# tower_controller.net
KiCad netlist of a schematic drawn in EAGLE
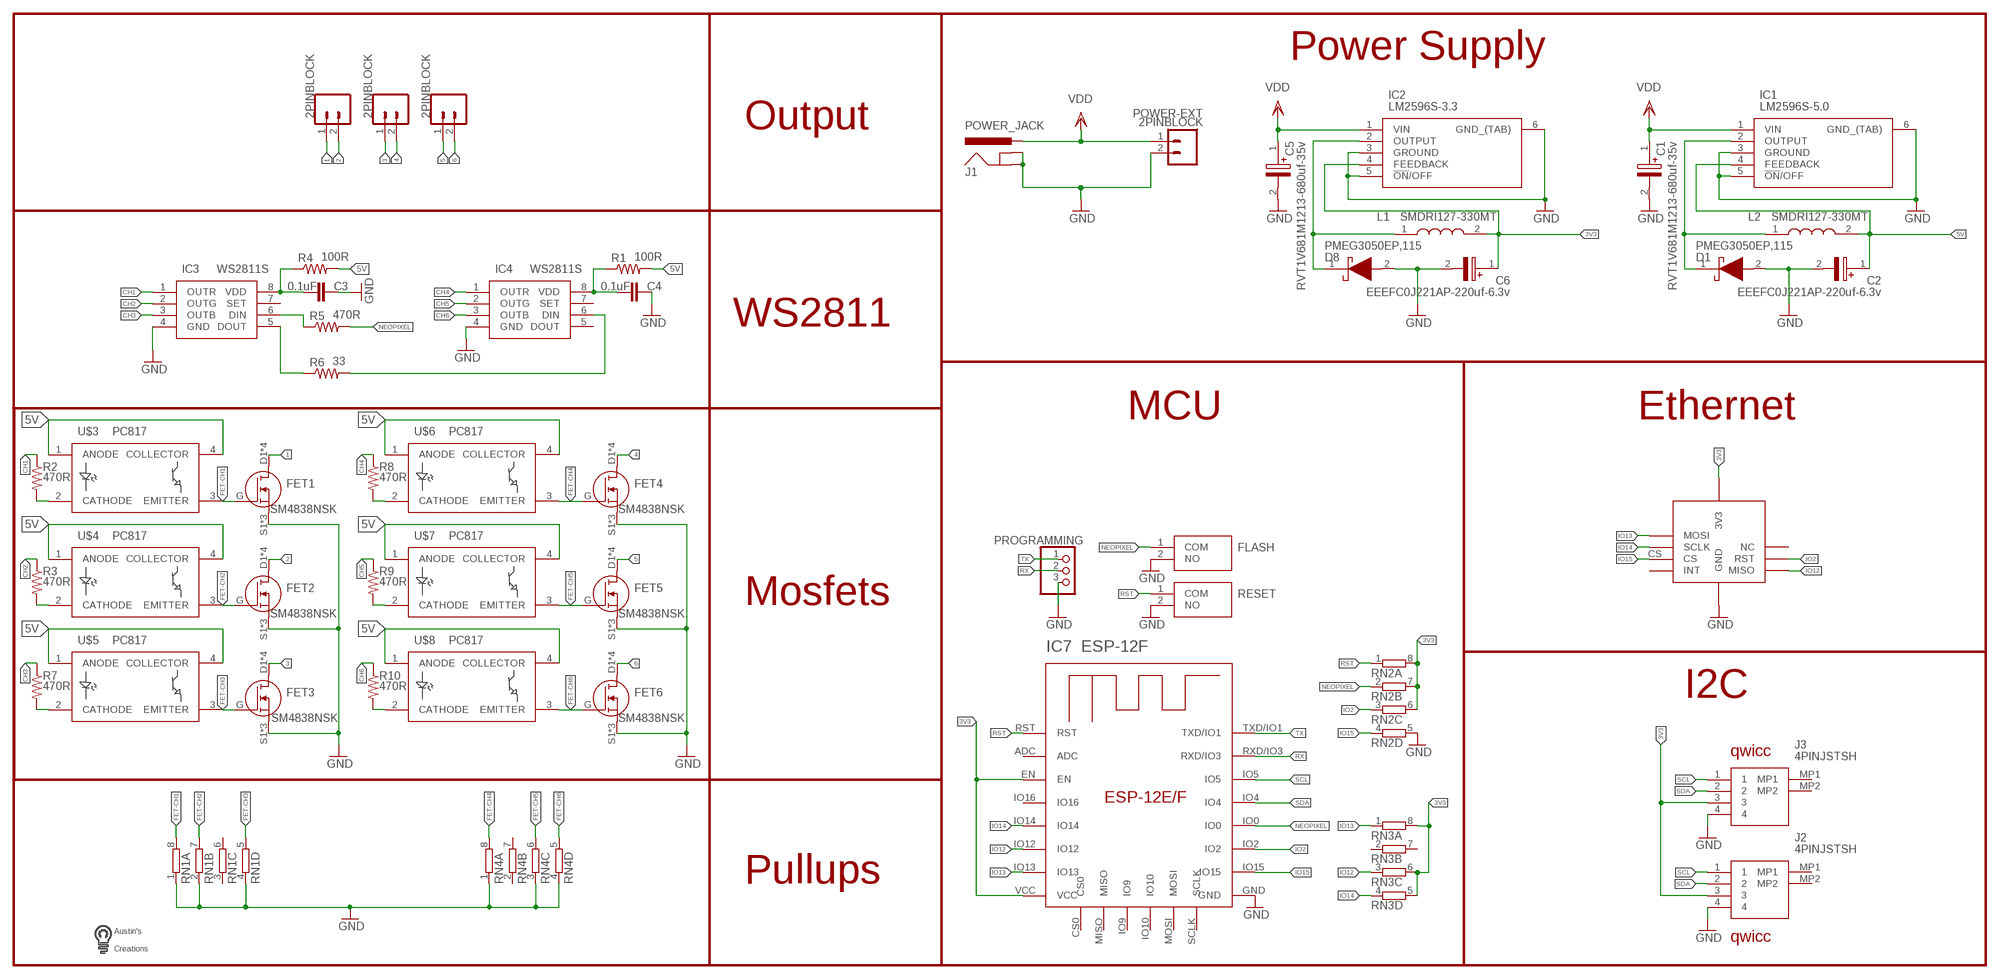
[diagram p0: schematic, sheet 1]

(export (version "E")
  (design (tool "Eeschema 10.0.6"))
  (components
    (comp (ref "C1")
      (value "RVT1V681M1213-680uf-35v")
      (footprint "eagle-import:CAPAE1350X1400N")
      (fields
        (field (name "MANUFACTURER_PART_NUMBER") "EEE-HD1V681AQ")
        (field (name "MOUSER_PART_NUMBER") "667-EEE-HD1V681AQ")
      )
      (libsource (lib "eagle-import") (part "EEE-HD1V681AQ"))
    )
    (comp (ref "C2")
      (value "EEEFC0J221AP-220uf-6.3v")
      (footprint "eagle-import:CAPAE830X650N")
      (fields (field (name "MANUFACTURER_PART_NUMBER") "EEEFC0J221AP"))
      (libsource (lib "eagle-import") (part "EEEFC0J221AP"))
    )
    (comp (ref "C3")
      (value "0.1uF")
      (footprint "eagle-import:C0603")
      (libsource (lib "eagle-import") (part "C-EUC0603"))
    )
    (comp (ref "C4")
      (value "0.1uF")
      (footprint "eagle-import:C0603")
      (libsource (lib "eagle-import") (part "C-EUC0603"))
    )
    (comp (ref "C5")
      (value "RVT1V681M1213-680uf-35v")
      (footprint "eagle-import:CAPAE1350X1400N")
      (fields
        (field (name "MANUFACTURER_PART_NUMBER") "EEE-HD1V681AQ")
        (field (name "MOUSER_PART_NUMBER") "667-EEE-HD1V681AQ")
      )
      (libsource (lib "eagle-import") (part "EEE-HD1V681AQ"))
    )
    (comp (ref "C6")
      (value "EEEFC0J221AP-220uf-6.3v")
      (footprint "eagle-import:CAPAE830X650N")
      (fields (field (name "MANUFACTURER_PART_NUMBER") "EEEFC0J221AP"))
      (libsource (lib "eagle-import") (part "EEEFC0J221AP"))
    )
    (comp (ref "D1")
      (value "PMEG3050EP,115")
      (footprint "eagle-import:PMEG3050EP115")
      (fields (field (name "MOUSER_PART_NUMBER") "771-PMEG3050EP115"))
      (libsource (lib "eagle-import") (part "PMEG3050EP,115"))
    )
    (comp (ref "D8")
      (value "PMEG3050EP,115")
      (footprint "eagle-import:PMEG3050EP115")
      (fields (field (name "MOUSER_PART_NUMBER") "771-PMEG3050EP115"))
      (libsource (lib "eagle-import") (part "PMEG3050EP,115"))
    )
    (comp (ref "FET1")
      (value "SM4838NSK")
      (footprint "eagle-import:SM4838NSK")
      (libsource (lib "eagle-import") (part "SM4838NSK"))
    )
    (comp (ref "FET2")
      (value "SM4838NSK")
      (footprint "eagle-import:SM4838NSK")
      (libsource (lib "eagle-import") (part "SM4838NSK"))
    )
    (comp (ref "FET3")
      (value "SM4838NSK")
      (footprint "eagle-import:SM4838NSK")
      (libsource (lib "eagle-import") (part "SM4838NSK"))
    )
    (comp (ref "FET4")
      (value "SM4838NSK")
      (footprint "eagle-import:SM4838NSK")
      (libsource (lib "eagle-import") (part "SM4838NSK"))
    )
    (comp (ref "FET5")
      (value "SM4838NSK")
      (footprint "eagle-import:SM4838NSK")
      (libsource (lib "eagle-import") (part "SM4838NSK"))
    )
    (comp (ref "FET6")
      (value "SM4838NSK")
      (footprint "eagle-import:SM4838NSK")
      (libsource (lib "eagle-import") (part "SM4838NSK"))
    )
    (comp (ref "FLASH")
      (value "PTS636_SM25F_SMTR_LFS")
      (footprint "eagle-import:PTS636SM25FSMTRLFS")
      (fields
        (field (name "ARROW_PART_NUMBER") "PTS636 SM25F SMTR LFS")
        (field (name "MOUSER_PART_NUMBER") "611-PTS636SM25FSMTRL")
      )
      (libsource (lib "eagle-import") (part "PTS636_SM25F_SMTR_LFS"))
    )
    (comp (ref "GND")
      (value "2PINBLOCK")
      (footprint "eagle-import:SCREWTERMINAL-5MM-2")
      (libsource (lib "eagle-import") (part "2PINBLOCK"))
    )
    (comp (ref "GND10")
      (value "2PINBLOCK")
      (footprint "eagle-import:SCREWTERMINAL-5MM-2")
      (libsource (lib "eagle-import") (part "2PINBLOCK"))
    )
    (comp (ref "GND11")
      (value "2PINBLOCK")
      (footprint "eagle-import:SCREWTERMINAL-5MM-2")
      (libsource (lib "eagle-import") (part "2PINBLOCK"))
    )
    (comp (ref "IC1")
      (value "LM2596S-5.0")
      (footprint "eagle-import:TO170P1435X465-6N")
      (fields
        (field (name "MANUFACTURER_PART_NUMBER") "LM2596S-3.3/NOPB")
        (field (name "MOUSER_PART_NUMBER") "926-LM2596S-3.3/NOPB")
      )
      (libsource (lib "eagle-import") (part "LM2596S-3.3_NOPB"))
    )
    (comp (ref "IC2")
      (value "LM2596S-3.3")
      (footprint "eagle-import:TO170P1435X465-6N")
      (fields
        (field (name "MANUFACTURER_PART_NUMBER") "LM2596S-3.3/NOPB")
        (field (name "MOUSER_PART_NUMBER") "926-LM2596S-3.3/NOPB")
      )
      (libsource (lib "eagle-import") (part "LM2596S-3.3_NOPB"))
    )
    (comp (ref "IC3")
      (value "WS2811S")
      (footprint "eagle-import:SOIC127P600X175-8N")
      (fields (field (name "MANUFACTURER_PART_NUMBER") "ws2811s"))
      (libsource (lib "eagle-import") (part "WS2811S"))
    )
    (comp (ref "IC4")
      (value "WS2811S")
      (footprint "eagle-import:SOIC127P600X175-8N")
      (fields (field (name "MANUFACTURER_PART_NUMBER") "ws2811s"))
      (libsource (lib "eagle-import") (part "WS2811S"))
    )
    (comp (ref "IC7")
      (value "ESP-12F")
      (footprint "eagle-import:ESP-12E")
      (libsource (lib "eagle-import") (part "ESP-12E/F"))
    )
    (comp (ref "J1")
      (value "POWER_JACK")
      (footprint "eagle-import:POWER_JACK_PTH")
      (libsource (lib "eagle-import") (part "POWER_JACK"))
    )
    (comp (ref "J2")
      (value "4PINJSTSH")
      (footprint "eagle-import:665104131822")
      (fields
        (field (name "MANUFACTURER_PART_NUMBER") "665104131822")
        (field (name "MOUSER_PART_NUMBER") "710-665104131822")
      )
      (libsource (lib "eagle-import") (part "4PINJSTSH"))
    )
    (comp (ref "J3")
      (value "4PINJSTSH")
      (footprint "eagle-import:665104131822")
      (fields
        (field (name "MANUFACTURER_PART_NUMBER") "665104131822")
        (field (name "MOUSER_PART_NUMBER") "710-665104131822")
      )
      (libsource (lib "eagle-import") (part "4PINJSTSH"))
    )
    (comp (ref "L1")
      (value "SMDRI127-330MT")
      (footprint "eagle-import:INDPM120120X800N")
      (fields
        (field (name "MANUFACTURER_PART_NUMBER") "CDRH127/LDNP-330MC")
        (field (name "MOUSER_PART_NUMBER") "851-CDRH127LDNP330MC")
      )
      (libsource (lib "eagle-import") (part "CDRH127_LDNP-330MC"))
    )
    (comp (ref "L2")
      (value "SMDRI127-330MT")
      (footprint "eagle-import:INDPM120120X800N")
      (fields
        (field (name "MANUFACTURER_PART_NUMBER") "CDRH127/LDNP-330MC")
        (field (name "MOUSER_PART_NUMBER") "851-CDRH127LDNP330MC")
      )
      (libsource (lib "eagle-import") (part "CDRH127_LDNP-330MC"))
    )
    (comp (ref "POWER-EXT")
      (value "2PINBLOCK")
      (footprint "eagle-import:SCREWTERMINAL-5MM-2")
      (libsource (lib "eagle-import") (part "2PINBLOCK"))
    )
    (comp (ref "PROGRAMMING")
      (value "PINHD-1X3")
      (footprint "eagle-import:1X03")
      (libsource (lib "eagle-import") (part "PINHD-1X3"))
    )
    (comp (ref "R1")
      (value "100R")
      (footprint "eagle-import:R0603")
      (libsource (lib "eagle-import") (part "R-US_R0603"))
    )
    (comp (ref "R2")
      (value "470R")
      (footprint "eagle-import:R0603")
      (libsource (lib "eagle-import") (part "R-US_R0603"))
    )
    (comp (ref "R3")
      (value "470R")
      (footprint "eagle-import:R0603")
      (libsource (lib "eagle-import") (part "R-US_R0603"))
    )
    (comp (ref "R4")
      (value "100R")
      (footprint "eagle-import:R0603")
      (libsource (lib "eagle-import") (part "R-US_R0603"))
    )
    (comp (ref "R5")
      (value "470R")
      (footprint "eagle-import:R0603")
      (libsource (lib "eagle-import") (part "R-US_R0603"))
    )
    (comp (ref "R6")
      (value "33")
      (footprint "eagle-import:R0603")
      (libsource (lib "eagle-import") (part "R-US_R0603"))
    )
    (comp (ref "R7")
      (value "470R")
      (footprint "eagle-import:R0603")
      (libsource (lib "eagle-import") (part "R-US_R0603"))
    )
    (comp (ref "R8")
      (value "470R")
      (footprint "eagle-import:R0603")
      (libsource (lib "eagle-import") (part "R-US_R0603"))
    )
    (comp (ref "R9")
      (value "470R")
      (footprint "eagle-import:R0603")
      (libsource (lib "eagle-import") (part "R-US_R0603"))
    )
    (comp (ref "R10")
      (value "470R")
      (footprint "eagle-import:R0603")
      (libsource (lib "eagle-import") (part "R-US_R0603"))
    )
    (comp (ref "RESET")
      (value "PTS636_SM25F_SMTR_LFS")
      (footprint "eagle-import:PTS636SM25FSMTRLFS")
      (fields
        (field (name "ARROW_PART_NUMBER") "PTS636 SM25F SMTR LFS")
        (field (name "MOUSER_PART_NUMBER") "611-PTS636SM25FSMTRL")
      )
      (libsource (lib "eagle-import") (part "PTS636_SM25F_SMTR_LFS"))
    )
    (comp (ref "RN1")
      (value "4R-N0603-ARC")
      (footprint "eagle-import:0603-ARC")
      (libsource (lib "eagle-import") (part "4R-N0603-ARC"))
    )
    (comp (ref "RN2")
      (value "4R-N0603-ARC")
      (footprint "eagle-import:0603-ARC")
      (libsource (lib "eagle-import") (part "4R-N0603-ARC"))
    )
    (comp (ref "RN3")
      (value "4R-N0603-ARC")
      (footprint "eagle-import:0603-ARC")
      (libsource (lib "eagle-import") (part "4R-N0603-ARC"))
    )
    (comp (ref "RN4")
      (value "4R-N0603-ARC")
      (footprint "eagle-import:0603-ARC")
      (libsource (lib "eagle-import") (part "4R-N0603-ARC"))
    )
    (comp (ref "U$1")
      (value "W5500MODULE")
      (footprint "eagle-import:W5500MODULE")
      (libsource (lib "eagle-import") (part "W5500MODULE"))
    )
    (comp (ref "U$2")
      (value "LOGOMED")
      (footprint "eagle-import:LOGOMED")
      (libsource (lib "eagle-import") (part "LOGOMED"))
    )
    (comp (ref "U$3")
      (value "PC817")
      (footprint "eagle-import:SOP254P960X420-4N")
      (libsource (lib "eagle-import") (part "PC817"))
    )
    (comp (ref "U$4")
      (value "PC817")
      (footprint "eagle-import:SOP254P960X420-4N")
      (libsource (lib "eagle-import") (part "PC817"))
    )
    (comp (ref "U$5")
      (value "PC817")
      (footprint "eagle-import:SOP254P960X420-4N")
      (libsource (lib "eagle-import") (part "PC817"))
    )
    (comp (ref "U$6")
      (value "PC817")
      (footprint "eagle-import:SOP254P960X420-4N")
      (libsource (lib "eagle-import") (part "PC817"))
    )
    (comp (ref "U$7")
      (value "PC817")
      (footprint "eagle-import:SOP254P960X420-4N")
      (libsource (lib "eagle-import") (part "PC817"))
    )
    (comp (ref "U$8")
      (value "PC817")
      (footprint "eagle-import:SOP254P960X420-4N")
      (libsource (lib "eagle-import") (part "PC817"))
    )
  )
  (nets
    (net (code "1") (name "1") (class "Default")
      (node (ref "FET1") (pin "D1") (pinfunction "D_D1") (pintype "bidirectional"))
      (node (ref "FET1") (pin "D2") (pinfunction "D_D2") (pintype "bidirectional"))
      (node (ref "FET1") (pin "D3") (pinfunction "D_D3") (pintype "bidirectional"))
      (node (ref "FET1") (pin "D4") (pinfunction "D_D4") (pintype "bidirectional"))
      (node (ref "GND") (pin "1") (pinfunction "1_1") (pintype "passive"))
    )
    (net (code "2") (name "2") (class "Default")
      (node (ref "FET2") (pin "D1") (pinfunction "D_D1") (pintype "bidirectional"))
      (node (ref "FET2") (pin "D2") (pinfunction "D_D2") (pintype "bidirectional"))
      (node (ref "FET2") (pin "D3") (pinfunction "D_D3") (pintype "bidirectional"))
      (node (ref "FET2") (pin "D4") (pinfunction "D_D4") (pintype "bidirectional"))
      (node (ref "GND") (pin "2") (pinfunction "2_2") (pintype "passive"))
    )
    (net (code "3") (name "3") (class "Default")
      (node (ref "FET3") (pin "D1") (pinfunction "D_D1") (pintype "bidirectional"))
      (node (ref "FET3") (pin "D2") (pinfunction "D_D2") (pintype "bidirectional"))
      (node (ref "FET3") (pin "D3") (pinfunction "D_D3") (pintype "bidirectional"))
      (node (ref "FET3") (pin "D4") (pinfunction "D_D4") (pintype "bidirectional"))
      (node (ref "GND10") (pin "1") (pinfunction "1_1") (pintype "passive"))
    )
    (net (code "4") (name "3V3") (class "Default")
      (node (ref "C6") (pin "1") (pinfunction "+_1") (pintype "bidirectional"))
      (node (ref "IC2") (pin "4") (pinfunction "FEEDBACK_4") (pintype "bidirectional"))
      (node (ref "IC7") (pin "EN") (pinfunction "EN_EN") (pintype "bidirectional"))
      (node (ref "IC7") (pin "VCC") (pinfunction "VCC_VCC") (pintype "power_in"))
      (node (ref "J2") (pin "3") (pinfunction "3_3") (pintype "bidirectional"))
      (node (ref "J3") (pin "3") (pinfunction "3_3") (pintype "bidirectional"))
      (node (ref "L1") (pin "2") (pinfunction "2_2") (pintype "bidirectional"))
      (node (ref "RN2") (pin "6") (pinfunction "2_6") (pintype "passive"))
      (node (ref "RN2") (pin "7") (pinfunction "2_7") (pintype "passive"))
      (node (ref "RN2") (pin "8") (pinfunction "2_8") (pintype "passive"))
      (node (ref "RN3") (pin "5") (pinfunction "2_5") (pintype "passive"))
      (node (ref "RN3") (pin "6") (pinfunction "2_6") (pintype "passive"))
      (node (ref "RN3") (pin "8") (pinfunction "2_8") (pintype "passive"))
      (node (ref "U$1") (pin "3V3_1") (pinfunction "3V3_3V3_1") (pintype "bidirectional"))
      (node (ref "U$1") (pin "3V3_2") (pinfunction "3V3_3V3_2") (pintype "bidirectional"))
    )
    (net (code "5") (name "4") (class "Default")
      (node (ref "FET4") (pin "D1") (pinfunction "D_D1") (pintype "bidirectional"))
      (node (ref "FET4") (pin "D2") (pinfunction "D_D2") (pintype "bidirectional"))
      (node (ref "FET4") (pin "D3") (pinfunction "D_D3") (pintype "bidirectional"))
      (node (ref "FET4") (pin "D4") (pinfunction "D_D4") (pintype "bidirectional"))
      (node (ref "GND10") (pin "2") (pinfunction "2_2") (pintype "passive"))
    )
    (net (code "6") (name "5") (class "Default")
      (node (ref "FET5") (pin "D1") (pinfunction "D_D1") (pintype "bidirectional"))
      (node (ref "FET5") (pin "D2") (pinfunction "D_D2") (pintype "bidirectional"))
      (node (ref "FET5") (pin "D3") (pinfunction "D_D3") (pintype "bidirectional"))
      (node (ref "FET5") (pin "D4") (pinfunction "D_D4") (pintype "bidirectional"))
      (node (ref "GND11") (pin "1") (pinfunction "1_1") (pintype "passive"))
    )
    (net (code "7") (name "5V") (class "Default")
      (node (ref "C2") (pin "1") (pinfunction "+_1") (pintype "bidirectional"))
      (node (ref "IC1") (pin "4") (pinfunction "FEEDBACK_4") (pintype "bidirectional"))
      (node (ref "L2") (pin "2") (pinfunction "2_2") (pintype "bidirectional"))
      (node (ref "R1") (pin "2") (pinfunction "2_2") (pintype "passive"))
      (node (ref "R4") (pin "2") (pinfunction "2_2") (pintype "passive"))
      (node (ref "U$3") (pin "1") (pinfunction "ANODE_1") (pintype "bidirectional"))
      (node (ref "U$3") (pin "4") (pinfunction "COLLECTOR_4") (pintype "bidirectional"))
      (node (ref "U$4") (pin "1") (pinfunction "ANODE_1") (pintype "bidirectional"))
      (node (ref "U$4") (pin "4") (pinfunction "COLLECTOR_4") (pintype "bidirectional"))
      (node (ref "U$5") (pin "1") (pinfunction "ANODE_1") (pintype "bidirectional"))
      (node (ref "U$5") (pin "4") (pinfunction "COLLECTOR_4") (pintype "bidirectional"))
      (node (ref "U$6") (pin "1") (pinfunction "ANODE_1") (pintype "bidirectional"))
      (node (ref "U$6") (pin "4") (pinfunction "COLLECTOR_4") (pintype "bidirectional"))
      (node (ref "U$7") (pin "1") (pinfunction "ANODE_1") (pintype "bidirectional"))
      (node (ref "U$7") (pin "4") (pinfunction "COLLECTOR_4") (pintype "bidirectional"))
      (node (ref "U$8") (pin "1") (pinfunction "ANODE_1") (pintype "bidirectional"))
      (node (ref "U$8") (pin "4") (pinfunction "COLLECTOR_4") (pintype "bidirectional"))
    )
    (net (code "8") (name "6") (class "Default")
      (node (ref "FET6") (pin "D1") (pinfunction "D_D1") (pintype "bidirectional"))
      (node (ref "FET6") (pin "D2") (pinfunction "D_D2") (pintype "bidirectional"))
      (node (ref "FET6") (pin "D3") (pinfunction "D_D3") (pintype "bidirectional"))
      (node (ref "FET6") (pin "D4") (pinfunction "D_D4") (pintype "bidirectional"))
      (node (ref "GND11") (pin "2") (pinfunction "2_2") (pintype "passive"))
    )
    (net (code "9") (name "CH1") (class "Default")
      (node (ref "IC3") (pin "1") (pinfunction "OUTR_1") (pintype "output"))
      (node (ref "R2") (pin "1") (pinfunction "1_1") (pintype "passive"))
    )
    (net (code "10") (name "CH2") (class "Default")
      (node (ref "IC3") (pin "2") (pinfunction "OUTG_2") (pintype "output"))
      (node (ref "R3") (pin "1") (pinfunction "1_1") (pintype "passive"))
    )
    (net (code "11") (name "CH3") (class "Default")
      (node (ref "IC3") (pin "3") (pinfunction "OUTB_3") (pintype "output"))
      (node (ref "R7") (pin "1") (pinfunction "1_1") (pintype "passive"))
    )
    (net (code "12") (name "CH4") (class "Default")
      (node (ref "IC4") (pin "1") (pinfunction "OUTR_1") (pintype "output"))
      (node (ref "R8") (pin "1") (pinfunction "1_1") (pintype "passive"))
    )
    (net (code "13") (name "CH5") (class "Default")
      (node (ref "IC4") (pin "2") (pinfunction "OUTG_2") (pintype "output"))
      (node (ref "R9") (pin "1") (pinfunction "1_1") (pintype "passive"))
    )
    (net (code "14") (name "CH6") (class "Default")
      (node (ref "IC4") (pin "3") (pinfunction "OUTB_3") (pintype "output"))
      (node (ref "R10") (pin "1") (pinfunction "1_1") (pintype "passive"))
    )
    (net (code "15") (name "FET-CH1") (class "Default")
      (node (ref "FET1") (pin "G") (pinfunction "G_G") (pintype "bidirectional"))
      (node (ref "RN1") (pin "8") (pinfunction "2_8") (pintype "passive"))
      (node (ref "U$3") (pin "3") (pinfunction "EMITTER_3") (pintype "bidirectional"))
    )
    (net (code "16") (name "FET-CH2") (class "Default")
      (node (ref "FET2") (pin "G") (pinfunction "G_G") (pintype "bidirectional"))
      (node (ref "RN1") (pin "7") (pinfunction "2_7") (pintype "passive"))
      (node (ref "U$4") (pin "3") (pinfunction "EMITTER_3") (pintype "bidirectional"))
    )
    (net (code "17") (name "FET-CH3") (class "Default")
      (node (ref "FET3") (pin "G") (pinfunction "G_G") (pintype "bidirectional"))
      (node (ref "RN1") (pin "5") (pinfunction "2_5") (pintype "passive"))
      (node (ref "U$5") (pin "3") (pinfunction "EMITTER_3") (pintype "bidirectional"))
    )
    (net (code "18") (name "FET-CH4") (class "Default")
      (node (ref "FET4") (pin "G") (pinfunction "G_G") (pintype "bidirectional"))
      (node (ref "RN4") (pin "8") (pinfunction "2_8") (pintype "passive"))
      (node (ref "U$6") (pin "3") (pinfunction "EMITTER_3") (pintype "bidirectional"))
    )
    (net (code "19") (name "FET-CH5") (class "Default")
      (node (ref "FET5") (pin "G") (pinfunction "G_G") (pintype "bidirectional"))
      (node (ref "RN4") (pin "6") (pinfunction "2_6") (pintype "passive"))
      (node (ref "U$7") (pin "3") (pinfunction "EMITTER_3") (pintype "bidirectional"))
    )
    (net (code "20") (name "FET-CH6") (class "Default")
      (node (ref "FET6") (pin "G") (pinfunction "G_G") (pintype "bidirectional"))
      (node (ref "RN4") (pin "5") (pinfunction "2_5") (pintype "passive"))
      (node (ref "U$8") (pin "3") (pinfunction "EMITTER_3") (pintype "bidirectional"))
    )
    (net (code "21") (name "GND") (class "Default")
      (node (ref "C1") (pin "2") (pinfunction "-_2") (pintype "bidirectional"))
      (node (ref "C2") (pin "2") (pinfunction "-_2") (pintype "bidirectional"))
      (node (ref "C3") (pin "1") (pinfunction "1_1") (pintype "passive"))
      (node (ref "C4") (pin "1") (pinfunction "1_1") (pintype "passive"))
      (node (ref "C5") (pin "2") (pinfunction "-_2") (pintype "bidirectional"))
      (node (ref "C6") (pin "2") (pinfunction "-_2") (pintype "bidirectional"))
      (node (ref "D1") (pin "2") (pinfunction "A_2") (pintype "bidirectional"))
      (node (ref "D8") (pin "2") (pinfunction "A_2") (pintype "bidirectional"))
      (node (ref "FET1") (pin "S1") (pinfunction "S_S1") (pintype "bidirectional"))
      (node (ref "FET1") (pin "S2") (pinfunction "S_S2") (pintype "bidirectional"))
      (node (ref "FET1") (pin "S3") (pinfunction "S_S3") (pintype "bidirectional"))
      (node (ref "FET2") (pin "S1") (pinfunction "S_S1") (pintype "bidirectional"))
      (node (ref "FET2") (pin "S2") (pinfunction "S_S2") (pintype "bidirectional"))
      (node (ref "FET2") (pin "S3") (pinfunction "S_S3") (pintype "bidirectional"))
      (node (ref "FET3") (pin "S1") (pinfunction "S_S1") (pintype "bidirectional"))
      (node (ref "FET3") (pin "S2") (pinfunction "S_S2") (pintype "bidirectional"))
      (node (ref "FET3") (pin "S3") (pinfunction "S_S3") (pintype "bidirectional"))
      (node (ref "FET4") (pin "S1") (pinfunction "S_S1") (pintype "bidirectional"))
      (node (ref "FET4") (pin "S2") (pinfunction "S_S2") (pintype "bidirectional"))
      (node (ref "FET4") (pin "S3") (pinfunction "S_S3") (pintype "bidirectional"))
      (node (ref "FET5") (pin "S1") (pinfunction "S_S1") (pintype "bidirectional"))
      (node (ref "FET5") (pin "S2") (pinfunction "S_S2") (pintype "bidirectional"))
      (node (ref "FET5") (pin "S3") (pinfunction "S_S3") (pintype "bidirectional"))
      (node (ref "FET6") (pin "S1") (pinfunction "S_S1") (pintype "bidirectional"))
      (node (ref "FET6") (pin "S2") (pinfunction "S_S2") (pintype "bidirectional"))
      (node (ref "FET6") (pin "S3") (pinfunction "S_S3") (pintype "bidirectional"))
      (node (ref "FLASH") (pin "2") (pinfunction "NO_2") (pintype "bidirectional"))
      (node (ref "IC1") (pin "3") (pinfunction "GROUND_3") (pintype "bidirectional"))
      (node (ref "IC1") (pin "5") (pinfunction "~{ON}/OFF_5") (pintype "bidirectional"))
      (node (ref "IC1") (pin "6") (pinfunction "GND_(TAB)_6") (pintype "power_in"))
      (node (ref "IC2") (pin "3") (pinfunction "GROUND_3") (pintype "bidirectional"))
      (node (ref "IC2") (pin "5") (pinfunction "~{ON}/OFF_5") (pintype "bidirectional"))
      (node (ref "IC2") (pin "6") (pinfunction "GND_(TAB)_6") (pintype "power_in"))
      (node (ref "IC3") (pin "4") (pinfunction "GND_4") (pintype "power_in"))
      (node (ref "IC4") (pin "4") (pinfunction "GND_4") (pintype "power_in"))
      (node (ref "IC7") (pin "GND") (pinfunction "GND_GND") (pintype "power_in"))
      (node (ref "J1") (pin "GND") (pinfunction "GND_GND") (pintype "bidirectional"))
      (node (ref "J1") (pin "GNDBREAK") (pinfunction "GNDBREAK_GNDBREAK") (pintype "bidirectional"))
      (node (ref "J2") (pin "4") (pinfunction "4_4") (pintype "bidirectional"))
      (node (ref "J3") (pin "4") (pinfunction "4_4") (pintype "bidirectional"))
      (node (ref "POWER-EXT") (pin "2") (pinfunction "2_2") (pintype "passive"))
      (node (ref "PROGRAMMING") (pin "3") (pinfunction "3_3") (pintype "passive"))
      (node (ref "RESET") (pin "2") (pinfunction "NO_2") (pintype "bidirectional"))
      (node (ref "RN1") (pin "1") (pinfunction "1_1") (pintype "passive"))
      (node (ref "RN1") (pin "2") (pinfunction "1_2") (pintype "passive"))
      (node (ref "RN1") (pin "4") (pinfunction "1_4") (pintype "passive"))
      (node (ref "RN2") (pin "5") (pinfunction "2_5") (pintype "passive"))
      (node (ref "RN4") (pin "1") (pinfunction "1_1") (pintype "passive"))
      (node (ref "RN4") (pin "3") (pinfunction "1_3") (pintype "passive"))
      (node (ref "RN4") (pin "4") (pinfunction "1_4") (pintype "passive"))
      (node (ref "U$1") (pin "GND1") (pinfunction "GND_GND1") (pintype "bidirectional"))
      (node (ref "U$1") (pin "GND2") (pinfunction "GND_GND2") (pintype "bidirectional"))
      (node (ref "U$1") (pin "GND3") (pinfunction "GND_GND3") (pintype "bidirectional"))
    )
    (net (code "22") (name "IO2") (class "Default")
      (node (ref "IC7") (pin "IO2") (pinfunction "IO2_IO2") (pintype "bidirectional"))
      (node (ref "RN2") (pin "3") (pinfunction "1_3") (pintype "passive"))
      (node (ref "U$1") (pin "RST") (pinfunction "RST_RST") (pintype "bidirectional"))
    )
    (net (code "23") (name "IO12") (class "Default")
      (node (ref "IC7") (pin "IO12") (pinfunction "IO12_IO12") (pintype "bidirectional"))
      (node (ref "RN3") (pin "3") (pinfunction "1_3") (pintype "passive"))
      (node (ref "U$1") (pin "MISO") (pinfunction "MISO_MISO") (pintype "bidirectional"))
    )
    (net (code "24") (name "IO13") (class "Default")
      (node (ref "IC7") (pin "IO13") (pinfunction "IO13_IO13") (pintype "bidirectional"))
      (node (ref "RN3") (pin "1") (pinfunction "1_1") (pintype "passive"))
      (node (ref "U$1") (pin "MOSI") (pinfunction "MOSI_MOSI") (pintype "bidirectional"))
    )
    (net (code "25") (name "IO14") (class "Default")
      (node (ref "IC7") (pin "IO14") (pinfunction "IO14_IO14") (pintype "bidirectional"))
      (node (ref "RN3") (pin "4") (pinfunction "1_4") (pintype "passive"))
      (node (ref "U$1") (pin "SCLK") (pinfunction "SCLK_SCLK") (pintype "bidirectional"))
    )
    (net (code "26") (name "IO15") (class "Default")
      (node (ref "IC7") (pin "IO15") (pinfunction "IO15_IO15") (pintype "bidirectional"))
      (node (ref "RN2") (pin "4") (pinfunction "1_4") (pintype "passive"))
      (node (ref "U$1") (pin "CS") (pinfunction "CS_CS") (pintype "bidirectional"))
    )
    (net (code "27") (name "NEOPIXEL") (class "Default")
      (node (ref "FLASH") (pin "1") (pinfunction "COM_1") (pintype "bidirectional"))
      (node (ref "IC7") (pin "IO0") (pinfunction "IO0_IO0") (pintype "bidirectional"))
      (node (ref "R5") (pin "2") (pinfunction "2_2") (pintype "passive"))
      (node (ref "RN2") (pin "2") (pinfunction "1_2") (pintype "passive"))
    )
    (net (code "28") (name "Net-(D1-K)") (class "Default")
      (node (ref "D1") (pin "1") (pinfunction "K_1") (pintype "bidirectional"))
      (node (ref "IC1") (pin "2") (pinfunction "OUTPUT_2") (pintype "output"))
      (node (ref "L2") (pin "1") (pinfunction "1_1") (pintype "bidirectional"))
    )
    (net (code "29") (name "Net-(D8-K)") (class "Default")
      (node (ref "D8") (pin "1") (pinfunction "K_1") (pintype "bidirectional"))
      (node (ref "IC2") (pin "2") (pinfunction "OUTPUT_2") (pintype "output"))
      (node (ref "L1") (pin "1") (pinfunction "1_1") (pintype "bidirectional"))
    )
    (net (code "30") (name "Net-(IC3-DIN)") (class "Default")
      (node (ref "IC3") (pin "6") (pinfunction "DIN_6") (pintype "input"))
      (node (ref "R5") (pin "1") (pinfunction "1_1") (pintype "passive"))
    )
    (net (code "31") (name "Net-(IC3-DOUT)") (class "Default")
      (node (ref "IC3") (pin "5") (pinfunction "DOUT_5") (pintype "bidirectional"))
      (node (ref "R6") (pin "1") (pinfunction "1_1") (pintype "passive"))
    )
    (net (code "32") (name "Net-(IC3-VDD)") (class "Default")
      (node (ref "C3") (pin "2") (pinfunction "2_2") (pintype "passive"))
      (node (ref "IC3") (pin "8") (pinfunction "VDD_8") (pintype "power_in"))
      (node (ref "R4") (pin "1") (pinfunction "1_1") (pintype "passive"))
    )
    (net (code "33") (name "Net-(IC4-DIN)") (class "Default")
      (node (ref "IC4") (pin "6") (pinfunction "DIN_6") (pintype "input"))
      (node (ref "R6") (pin "2") (pinfunction "2_2") (pintype "passive"))
    )
    (net (code "34") (name "Net-(IC4-VDD)") (class "Default")
      (node (ref "C4") (pin "2") (pinfunction "2_2") (pintype "passive"))
      (node (ref "IC4") (pin "8") (pinfunction "VDD_8") (pintype "power_in"))
      (node (ref "R1") (pin "1") (pinfunction "1_1") (pintype "passive"))
    )
    (net (code "35") (name "Net-(U$3-CATHODE)") (class "Default")
      (node (ref "R2") (pin "2") (pinfunction "2_2") (pintype "passive"))
      (node (ref "U$3") (pin "2") (pinfunction "CATHODE_2") (pintype "bidirectional"))
    )
    (net (code "36") (name "Net-(U$4-CATHODE)") (class "Default")
      (node (ref "R3") (pin "2") (pinfunction "2_2") (pintype "passive"))
      (node (ref "U$4") (pin "2") (pinfunction "CATHODE_2") (pintype "bidirectional"))
    )
    (net (code "37") (name "Net-(U$5-CATHODE)") (class "Default")
      (node (ref "R7") (pin "2") (pinfunction "2_2") (pintype "passive"))
      (node (ref "U$5") (pin "2") (pinfunction "CATHODE_2") (pintype "bidirectional"))
    )
    (net (code "38") (name "Net-(U$6-CATHODE)") (class "Default")
      (node (ref "R8") (pin "2") (pinfunction "2_2") (pintype "passive"))
      (node (ref "U$6") (pin "2") (pinfunction "CATHODE_2") (pintype "bidirectional"))
    )
    (net (code "39") (name "Net-(U$7-CATHODE)") (class "Default")
      (node (ref "R9") (pin "2") (pinfunction "2_2") (pintype "passive"))
      (node (ref "U$7") (pin "2") (pinfunction "CATHODE_2") (pintype "bidirectional"))
    )
    (net (code "40") (name "Net-(U$8-CATHODE)") (class "Default")
      (node (ref "R10") (pin "2") (pinfunction "2_2") (pintype "passive"))
      (node (ref "U$8") (pin "2") (pinfunction "CATHODE_2") (pintype "bidirectional"))
    )
    (net (code "41") (name "RST") (class "Default")
      (node (ref "IC7") (pin "RST") (pinfunction "RST_RST") (pintype "input"))
      (node (ref "RESET") (pin "1") (pinfunction "COM_1") (pintype "bidirectional"))
      (node (ref "RN2") (pin "1") (pinfunction "1_1") (pintype "passive"))
    )
    (net (code "42") (name "RX") (class "Default")
      (node (ref "IC7") (pin "RXD/IO3") (pinfunction "RXD/IO3_RXD/IO3") (pintype "bidirectional"))
      (node (ref "PROGRAMMING") (pin "2") (pinfunction "2_2") (pintype "passive"))
    )
    (net (code "43") (name "SCL") (class "Default")
      (node (ref "IC7") (pin "IO5") (pinfunction "IO5_IO5") (pintype "bidirectional"))
      (node (ref "J2") (pin "1") (pinfunction "1_1") (pintype "bidirectional"))
      (node (ref "J3") (pin "1") (pinfunction "1_1") (pintype "bidirectional"))
    )
    (net (code "44") (name "SDA") (class "Default")
      (node (ref "IC7") (pin "IO4") (pinfunction "IO4_IO4") (pintype "bidirectional"))
      (node (ref "J2") (pin "2") (pinfunction "2_2") (pintype "bidirectional"))
      (node (ref "J3") (pin "2") (pinfunction "2_2") (pintype "bidirectional"))
    )
    (net (code "45") (name "TX") (class "Default")
      (node (ref "IC7") (pin "TXD/IO1") (pinfunction "TXD/IO1_TXD/IO1") (pintype "bidirectional"))
      (node (ref "PROGRAMMING") (pin "1") (pinfunction "1_1") (pintype "passive"))
    )
    (net (code "46") (name "VDD") (class "Default")
      (node (ref "C1") (pin "1") (pinfunction "+_1") (pintype "bidirectional"))
      (node (ref "C5") (pin "1") (pinfunction "+_1") (pintype "bidirectional"))
      (node (ref "IC1") (pin "1") (pinfunction "VIN_1") (pintype "input"))
      (node (ref "IC2") (pin "1") (pinfunction "VIN_1") (pintype "input"))
      (node (ref "J1") (pin "PWR") (pinfunction "PWR_PWR") (pintype "bidirectional"))
      (node (ref "POWER-EXT") (pin "1") (pinfunction "1_1") (pintype "passive"))
    )
    (net (code "47") (name "unconnected-(IC3-SET-Pad7)") (class "Default")
      (node (ref "IC3") (pin "7") (pinfunction "SET_7") (pintype "input"))
    )
    (net (code "48") (name "unconnected-(IC4-DOUT-Pad5)") (class "Default")
      (node (ref "IC4") (pin "5") (pinfunction "DOUT_5") (pintype "bidirectional"))
    )
    (net (code "49") (name "unconnected-(IC4-SET-Pad7)") (class "Default")
      (node (ref "IC4") (pin "7") (pinfunction "SET_7") (pintype "input"))
    )
    (net (code "50") (name "unconnected-(IC7-PadADC)") (class "Default")
      (node (ref "IC7") (pin "ADC") (pinfunction "ADC_ADC") (pintype "bidirectional"))
    )
    (net (code "51") (name "unconnected-(IC7-PadCS0)") (class "Default")
      (node (ref "IC7") (pin "CS0") (pinfunction "CS0_CS0") (pintype "bidirectional"))
    )
    (net (code "52") (name "unconnected-(IC7-PadIO9)") (class "Default")
      (node (ref "IC7") (pin "IO9") (pinfunction "IO9_IO9") (pintype "bidirectional"))
    )
    (net (code "53") (name "unconnected-(IC7-PadIO10)") (class "Default")
      (node (ref "IC7") (pin "IO10") (pinfunction "IO10_IO10") (pintype "bidirectional"))
    )
    (net (code "54") (name "unconnected-(IC7-PadIO16)") (class "Default")
      (node (ref "IC7") (pin "IO16") (pinfunction "IO16_IO16") (pintype "bidirectional"))
    )
    (net (code "55") (name "unconnected-(IC7-PadMISO)") (class "Default")
      (node (ref "IC7") (pin "MISO") (pinfunction "MISO_MISO") (pintype "bidirectional"))
    )
    (net (code "56") (name "unconnected-(IC7-PadMOSI)") (class "Default")
      (node (ref "IC7") (pin "MOSI") (pinfunction "MOSI_MOSI") (pintype "bidirectional"))
    )
    (net (code "57") (name "unconnected-(IC7-PadSCLK)") (class "Default")
      (node (ref "IC7") (pin "SCLK") (pinfunction "SCLK_SCLK") (pintype "bidirectional"))
    )
    (net (code "58") (name "unconnected-(J2-PadMP1)") (class "Default")
      (node (ref "J2") (pin "MP1") (pinfunction "MP1_MP1") (pintype "bidirectional"))
    )
    (net (code "59") (name "unconnected-(J2-PadMP2)") (class "Default")
      (node (ref "J2") (pin "MP2") (pinfunction "MP2_MP2") (pintype "bidirectional"))
    )
    (net (code "60") (name "unconnected-(J3-PadMP1)") (class "Default")
      (node (ref "J3") (pin "MP1") (pinfunction "MP1_MP1") (pintype "bidirectional"))
    )
    (net (code "61") (name "unconnected-(J3-PadMP2)") (class "Default")
      (node (ref "J3") (pin "MP2") (pinfunction "MP2_MP2") (pintype "bidirectional"))
    )
    (net (code "62") (name "unconnected-(RN1C-1-Pad3)") (class "Default")
      (node (ref "RN1") (pin "3") (pinfunction "1_3") (pintype "passive"))
    )
    (net (code "63") (name "unconnected-(RN1C-2-Pad6)") (class "Default")
      (node (ref "RN1") (pin "6") (pinfunction "2_6") (pintype "passive"))
    )
    (net (code "64") (name "unconnected-(RN3B-1-Pad2)") (class "Default")
      (node (ref "RN3") (pin "2") (pinfunction "1_2") (pintype "passive"))
    )
    (net (code "65") (name "unconnected-(RN3B-2-Pad7)") (class "Default")
      (node (ref "RN3") (pin "7") (pinfunction "2_7") (pintype "passive"))
    )
    (net (code "66") (name "unconnected-(RN4B-1-Pad2)") (class "Default")
      (node (ref "RN4") (pin "2") (pinfunction "1_2") (pintype "passive"))
    )
    (net (code "67") (name "unconnected-(RN4B-2-Pad7)") (class "Default")
      (node (ref "RN4") (pin "7") (pinfunction "2_7") (pintype "passive"))
    )
    (net (code "68") (name "unconnected-(U$1-PadINT)") (class "Default")
      (node (ref "U$1") (pin "INT") (pinfunction "INT_INT") (pintype "bidirectional"))
    )
    (net (code "69") (name "unconnected-(U$1-PadNC)") (class "Default")
      (node (ref "U$1") (pin "NC") (pinfunction "NC_NC") (pintype "no_connect"))
    )
  )
)
